# power.net
KiCad netlist of a schematic drawn in Altium Designer
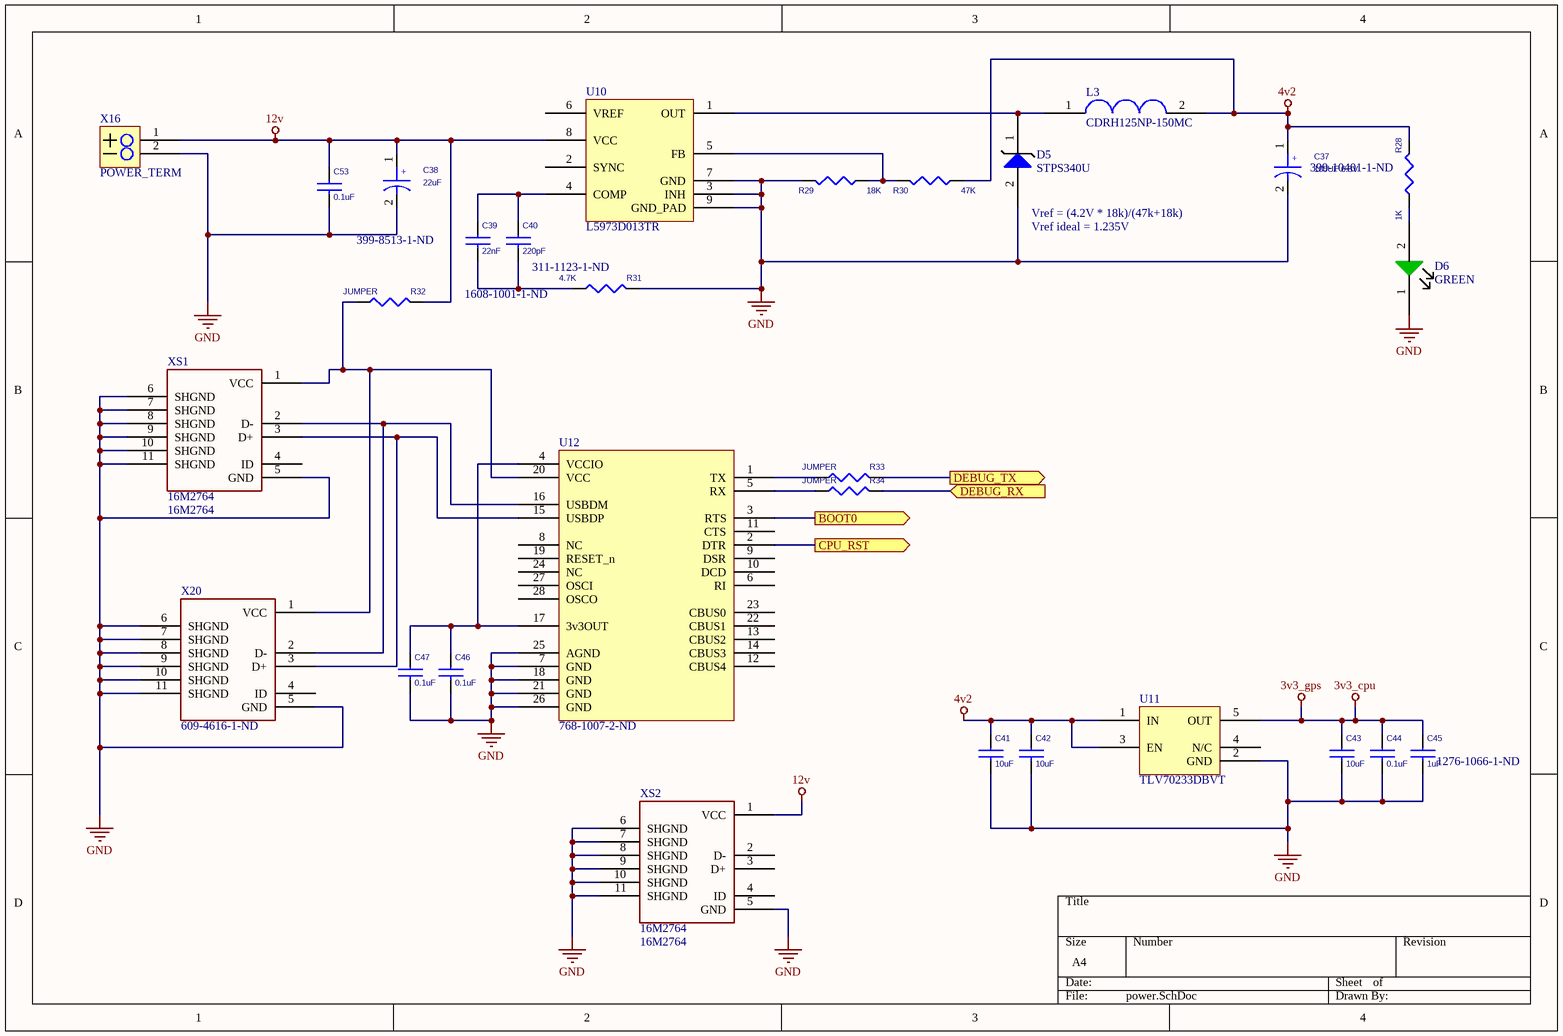
[diagram p0: power.SchDoc]

(export (version "E")
  (design (tool "Eeschema 10.0.6"))
  (components
    (comp (ref "C37")
      (value "100UF 6.3V")
      (footprint "CAPMP6133X31N")
      (description "CAP 100uF; 6.3V; Case: C; ESR:150mOhm")
      (fields (field (name "SUPPLIER PART NUMBER 1") "399-10401-1-ND"))
      (libsource (lib "Capacitors") (part "CAP_SMD_100UF_10%"))
    )
    (comp (ref "C38")
      (value "22uF")
      (footprint "CAPMP7143X31N")
      (description "CAP SMD 35volts 22uF 10% ESR=300mOhms")
      (fields (field (name "SUPPLIER PART NUMBER 1") "399-8513-1-ND"))
      (libsource (lib "Capacitors") (part "CAP_SMD_22UF_10%"))
    )
    (comp (ref "C39")
      (value "22nF")
      (footprint "CAPC2012X09M")
      (description "CAP 22NF 50V 10% X7R 0805")
      (fields (field (name "SUPPLIER PART NUMBER 1") "1608-1001-1-ND"))
      (libsource (lib "Capacitors") (part "CAP_SMD_22nF_10%"))
    )
    (comp (ref "C40")
      (value "220pF")
      (footprint "CAPC2012X09M")
      (description "CAP 220PF 50V 10%  0805")
      (fields (field (name "SUPPLIER PART NUMBER 1") "311-1123-1-ND"))
      (libsource (lib "Capacitors") (part "CAP_SMD_220pF_10%"))
    )
    (comp (ref "C41")
      (value "10uF")
      (footprint "CAPC2012X09M")
      (description "CAP CER 10UF 16V 20% X5R 0805")
      (libsource (lib "Capacitors") (part "CAP_SMD_10UF_20%"))
    )
    (comp (ref "C42")
      (value "10uF")
      (footprint "CAPC2012X09M")
      (description "CAP CER 10UF 16V 20% X5R 0805")
      (libsource (lib "Capacitors") (part "CAP_SMD_10UF_20%"))
    )
    (comp (ref "C43")
      (value "10uF")
      (footprint "CAPC2012X09M")
      (description "CAP CER 10UF 16V 20% X5R 0805")
      (libsource (lib "Capacitors") (part "CAP_SMD_10UF_20%"))
    )
    (comp (ref "C44")
      (value "0.1uF")
      (footprint "CAPC2012X09M")
      (description "CAP CER 0.1UF 25V 10% X7R 0805")
      (libsource (lib "Capacitors") (part "CAP_SMD_0.1UF_10%"))
    )
    (comp (ref "C45")
      (value "1uF")
      (footprint "CAPC2012X09M")
      (description "MLCC; 1uF; 25V; X7R; ±10%; SMD; 0805;")
      (fields (field (name "SUPPLIER PART NUMBER 1") "1276-1066-1-ND"))
      (libsource (lib "Capacitors") (part "CAP_SMD_1uF_10%"))
    )
    (comp (ref "C46")
      (value "0.1uF")
      (footprint "CAPC2012X09M")
      (description "CAP CER 0.1UF 25V 10% X7R 0805")
      (libsource (lib "Capacitors") (part "CAP_SMD_0.1UF_10%"))
    )
    (comp (ref "C47")
      (value "0.1uF")
      (footprint "CAPC2012X09M")
      (description "CAP CER 0.1UF 25V 10% X7R 0805")
      (libsource (lib "Capacitors") (part "CAP_SMD_0.1UF_10%"))
    )
    (comp (ref "C53")
      (value "0.1uF")
      (footprint "CAPC2012X09M")
      (description "CAP CER 0.1UF 25V 10% X7R 0805")
      (libsource (lib "Capacitors") (part "CAP_SMD_0.1UF_10%"))
    )
    (comp (ref "D5")
      (value "STPS340U")
      (footprint "SODFL535X265-2N")
      (description "DIODE, ZENER, 20V, 3W")
      (libsource (lib "Passive") (part "STPS340U"))
    )
    (comp (ref "D6")
      (value "GREEN")
      (footprint "DIOC2012X11N")
      (libsource (lib "Passive") (part "LED_GREEN"))
    )
    (comp (ref "L3")
      (value "CDRH125NP-150MC")
      (footprint "INDP123123X40N_SUMIDA")
      (libsource (lib "Passive") (part "IND_15uH_3.3A"))
    )
    (comp (ref "R28")
      (value "1K")
      (footprint "RESC2013X06M")
      (description "RES - 1K OHM, 5%, 1/8W, 0805 SMD")
      (libsource (lib "Resistors") (part "RES_SMD_1K_5%"))
    )
    (comp (ref "R29")
      (value "18K")
      (footprint "RESC2013X06M")
      (description "RES 18K OHM 1/8W 1% 0805 SMD")
      (libsource (lib "Resistors") (part "RES_SMD_18K_1%"))
    )
    (comp (ref "R30")
      (value "47K")
      (footprint "RESC2013X06M")
      (description "RES 47K OHM 1/8W 1% 0805")
      (libsource (lib "Resistors") (part "RES_SMD_47K_1%"))
    )
    (comp (ref "R31")
      (value "4.7K")
      (footprint "RESC2013X06M")
      (description "RES 4.7K OHM 1/8W 1% 0805 SMD")
      (libsource (lib "Resistors") (part "RES_SMD_4.7K_1%"))
    )
    (comp (ref "R32")
      (value "JUMPER")
      (footprint "RESC2013X06M_CMEASURE")
      (description "RES 0.0 OHM 1/8W JUMP 0805 SMD")
      (libsource (lib "Resistors") (part "RES_SMD_0_CURRENT"))
    )
    (comp (ref "R33")
      (value "JUMPER")
      (footprint "RESC2013X06M_CMEASURE")
      (description "RES 0.0 OHM 1/8W JUMP 0805 SMD")
      (libsource (lib "Resistors") (part "RES_SMD_0_CURRENT"))
    )
    (comp (ref "R34")
      (value "JUMPER")
      (footprint "RESC2013X06M_CMEASURE")
      (description "RES 0.0 OHM 1/8W JUMP 0805 SMD")
      (libsource (lib "Resistors") (part "RES_SMD_0_CURRENT"))
    )
    (comp (ref "U10")
      (value "L5973D013TR")
      (footprint "SOIC127P600X175_HS-9N")
      (description "IC REG BUCK ADJ 2.5A SOIC8")
      (libsource (lib "TruthEar") (part "L5973D013TR"))
    )
    (comp (ref "U11")
      (value "TLV70233DBVT")
      (footprint "SOT95P280X145-5M")
      (libsource (lib "TruthEar") (part "TLV70233DBVT"))
    )
    (comp (ref "U12")
      (value "FT232RL")
      (footprint "SOP65P780X200-28M")
      (fields (field (name "SUPPLIER PART NUMBER 1") "768-1007-2-ND"))
      (libsource (lib "TruthEar") (part "FT232RL"))
    )
    (comp (ref "X16")
      (value "POWER_TERM")
      (footprint "PH5")
      (libsource (lib "Connectors") (part "POWER_TERM"))
    )
    (comp (ref "X20")
      (value "10118193-0001LF")
      (footprint "USB_MICRO_10118193")
      (fields (field (name "SUPPLIER PART NUMBER 1") "609-4616-1-ND"))
      (libsource (lib "Connectors") (part "USB_MICRO"))
    )
    (comp (ref "XS1")
      (value "16M2764")
      (footprint "USB_MINI_16M2764")
      (fields (field (name "SUPPLIER PART NUMBER 1") "16M2764"))
      (libsource (lib "Connectors") (part "USB_MINI_16M2764"))
    )
    (comp (ref "XS2")
      (value "16M2764")
      (footprint "USB_MINI_16M2764")
      (fields (field (name "SUPPLIER PART NUMBER 1") "16M2764"))
      (libsource (lib "Connectors") (part "USB_MINI_16M2764"))
    )
  )
  (nets
    (net (code "1") (name "/BOOT0") (class "Default")
      (node (ref "U12") (pin "3") (pinfunction "RTS_3") (pintype "power_in"))
    )
    (net (code "2") (name "/CPU_RST") (class "Default")
      (node (ref "U12") (pin "2") (pinfunction "DTR_2") (pintype "power_in"))
    )
    (net (code "3") (name "/DEBUG_RX") (class "Default")
      (node (ref "R34") (pin "2") (pinfunction "2_2") (pintype "passive"))
    )
    (net (code "4") (name "/DEBUG_TX") (class "Default")
      (node (ref "R33") (pin "2") (pinfunction "2_2") (pintype "passive"))
    )
    (net (code "5") (name "3v3_cpu") (class "Default")
      (node (ref "C43") (pin "1") (pinfunction "1_1") (pintype "passive"))
      (node (ref "C44") (pin "1") (pinfunction "1_1") (pintype "passive"))
      (node (ref "C45") (pin "1") (pinfunction "1_1") (pintype "passive"))
      (node (ref "U11") (pin "5") (pinfunction "OUT_5") (pintype "passive"))
    )
    (net (code "6") (name "4v2") (class "Default")
      (node (ref "C37") (pin "1") (pinfunction "1_1") (pintype "passive"))
      (node (ref "C41") (pin "1") (pinfunction "1_1") (pintype "passive"))
      (node (ref "C42") (pin "1") (pinfunction "1_1") (pintype "passive"))
      (node (ref "L3") (pin "2") (pinfunction "2_2") (pintype "passive"))
      (node (ref "R28") (pin "2") (pinfunction "2_2") (pintype "passive"))
      (node (ref "R30") (pin "1") (pinfunction "1_1") (pintype "passive"))
      (node (ref "U11") (pin "1") (pinfunction "IN_1") (pintype "passive"))
      (node (ref "U11") (pin "3") (pinfunction "EN_3") (pintype "passive"))
    )
    (net (code "7") (name "12v") (class "Default")
      (node (ref "C38") (pin "1") (pinfunction "1_1") (pintype "passive"))
      (node (ref "C53") (pin "1") (pinfunction "1_1") (pintype "passive"))
      (node (ref "R32") (pin "2") (pinfunction "2_2") (pintype "passive"))
      (node (ref "U10") (pin "8") (pinfunction "VCC_8") (pintype "passive"))
      (node (ref "X16") (pin "1") (pinfunction "1_1") (pintype "passive"))
      (node (ref "XS2") (pin "1") (pinfunction "VCC_1") (pintype "passive"))
    )
    (net (code "8") (name "GND") (class "Default")
      (node (ref "C37") (pin "2") (pinfunction "2_2") (pintype "passive"))
      (node (ref "C38") (pin "2") (pinfunction "2_2") (pintype "passive"))
      (node (ref "C41") (pin "2") (pinfunction "2_2") (pintype "passive"))
      (node (ref "C42") (pin "2") (pinfunction "2_2") (pintype "passive"))
      (node (ref "C43") (pin "2") (pinfunction "2_2") (pintype "passive"))
      (node (ref "C44") (pin "2") (pinfunction "2_2") (pintype "passive"))
      (node (ref "C45") (pin "2") (pinfunction "2_2") (pintype "passive"))
      (node (ref "C46") (pin "2") (pinfunction "2_2") (pintype "passive"))
      (node (ref "C47") (pin "2") (pinfunction "2_2") (pintype "passive"))
      (node (ref "C53") (pin "2") (pinfunction "2_2") (pintype "passive"))
      (node (ref "D5") (pin "2") (pinfunction "A_2") (pintype "passive"))
      (node (ref "D6") (pin "1") (pinfunction "C_1") (pintype "passive"))
      (node (ref "R29") (pin "2") (pinfunction "2_2") (pintype "passive"))
      (node (ref "R31") (pin "2") (pinfunction "2_2") (pintype "passive"))
      (node (ref "U10") (pin "3") (pinfunction "INH_3") (pintype "passive"))
      (node (ref "U10") (pin "7") (pinfunction "GND_7") (pintype "passive"))
      (node (ref "U10") (pin "9") (pinfunction "GND_PAD_9") (pintype "passive"))
      (node (ref "U11") (pin "2") (pinfunction "GND_2") (pintype "passive"))
      (node (ref "U12") (pin "18") (pinfunction "GND_18") (pintype "power_in"))
      (node (ref "U12") (pin "21") (pinfunction "GND_21") (pintype "power_in"))
      (node (ref "U12") (pin "25") (pinfunction "AGND_25") (pintype "power_in"))
      (node (ref "U12") (pin "26") (pinfunction "GND_26") (pintype "power_in"))
      (node (ref "U12") (pin "7") (pinfunction "GND_7") (pintype "power_in"))
      (node (ref "X16") (pin "2") (pinfunction "2_2") (pintype "passive"))
      (node (ref "X20") (pin "10") (pinfunction "SHGND_10") (pintype "passive"))
      (node (ref "X20") (pin "11") (pinfunction "SHGND_11") (pintype "passive"))
      (node (ref "X20") (pin "5") (pinfunction "GND_5") (pintype "passive"))
      (node (ref "X20") (pin "6") (pinfunction "SHGND_6") (pintype "passive"))
      (node (ref "X20") (pin "7") (pinfunction "SHGND_7") (pintype "passive"))
      (node (ref "X20") (pin "8") (pinfunction "SHGND_8") (pintype "passive"))
      (node (ref "X20") (pin "9") (pinfunction "SHGND_9") (pintype "passive"))
      (node (ref "XS1") (pin "10") (pinfunction "SHGND_10") (pintype "passive"))
      (node (ref "XS1") (pin "11") (pinfunction "SHGND_11") (pintype "passive"))
      (node (ref "XS1") (pin "5") (pinfunction "GND_5") (pintype "passive"))
      (node (ref "XS1") (pin "6") (pinfunction "SHGND_6") (pintype "passive"))
      (node (ref "XS1") (pin "7") (pinfunction "SHGND_7") (pintype "passive"))
      (node (ref "XS1") (pin "8") (pinfunction "SHGND_8") (pintype "passive"))
      (node (ref "XS1") (pin "9") (pinfunction "SHGND_9") (pintype "passive"))
      (node (ref "XS2") (pin "10") (pinfunction "SHGND_10") (pintype "passive"))
      (node (ref "XS2") (pin "11") (pinfunction "SHGND_11") (pintype "passive"))
      (node (ref "XS2") (pin "5") (pinfunction "GND_5") (pintype "passive"))
      (node (ref "XS2") (pin "6") (pinfunction "SHGND_6") (pintype "passive"))
      (node (ref "XS2") (pin "7") (pinfunction "SHGND_7") (pintype "passive"))
      (node (ref "XS2") (pin "8") (pinfunction "SHGND_8") (pintype "passive"))
      (node (ref "XS2") (pin "9") (pinfunction "SHGND_9") (pintype "passive"))
    )
    (net (code "9") (name "Net-(C39-Pad2)") (class "Default")
      (node (ref "C39") (pin "2") (pinfunction "2_2") (pintype "passive"))
      (node (ref "C40") (pin "2") (pinfunction "2_2") (pintype "passive"))
      (node (ref "R31") (pin "1") (pinfunction "1_1") (pintype "passive"))
    )
    (net (code "10") (name "Net-(D5-C)") (class "Default")
      (node (ref "D5") (pin "1") (pinfunction "C_1") (pintype "passive"))
      (node (ref "L3") (pin "1") (pinfunction "1_1") (pintype "passive"))
      (node (ref "U10") (pin "1") (pinfunction "OUT_1") (pintype "passive"))
    )
    (net (code "11") (name "Net-(D6-A)") (class "Default")
      (node (ref "D6") (pin "2") (pinfunction "A_2") (pintype "passive"))
      (node (ref "R28") (pin "1") (pinfunction "1_1") (pintype "passive"))
    )
    (net (code "12") (name "Net-(U10-COMP)") (class "Default")
      (node (ref "C39") (pin "1") (pinfunction "1_1") (pintype "passive"))
      (node (ref "C40") (pin "1") (pinfunction "1_1") (pintype "passive"))
      (node (ref "U10") (pin "4") (pinfunction "COMP_4") (pintype "passive"))
    )
    (net (code "13") (name "Net-(U10-FB)") (class "Default")
      (node (ref "R29") (pin "1") (pinfunction "1_1") (pintype "passive"))
      (node (ref "R30") (pin "2") (pinfunction "2_2") (pintype "passive"))
      (node (ref "U10") (pin "5") (pinfunction "FB_5") (pintype "passive"))
    )
    (net (code "14") (name "Net-(U12-3v3OUT)") (class "Default")
      (node (ref "C46") (pin "1") (pinfunction "1_1") (pintype "passive"))
      (node (ref "C47") (pin "1") (pinfunction "1_1") (pintype "passive"))
      (node (ref "U12") (pin "17") (pinfunction "3v3OUT_17") (pintype "power_in"))
      (node (ref "U12") (pin "4") (pinfunction "VCCIO_4") (pintype "power_in"))
    )
    (net (code "15") (name "Net-(U12-RX)") (class "Default")
      (node (ref "R34") (pin "1") (pinfunction "1_1") (pintype "passive"))
      (node (ref "U12") (pin "5") (pinfunction "RX_5") (pintype "power_in"))
    )
    (net (code "16") (name "Net-(U12-TX)") (class "Default")
      (node (ref "R33") (pin "1") (pinfunction "1_1") (pintype "passive"))
      (node (ref "U12") (pin "1") (pinfunction "TX_1") (pintype "power_in"))
    )
    (net (code "17") (name "Net-(U12-USBDM)") (class "Default")
      (node (ref "U12") (pin "16") (pinfunction "USBDM_16") (pintype "power_in"))
      (node (ref "X20") (pin "2") (pinfunction "D-_2") (pintype "passive"))
      (node (ref "XS1") (pin "2") (pinfunction "D-_2") (pintype "passive"))
    )
    (net (code "18") (name "Net-(U12-USBDP)") (class "Default")
      (node (ref "U12") (pin "15") (pinfunction "USBDP_15") (pintype "power_in"))
      (node (ref "X20") (pin "3") (pinfunction "D+_3") (pintype "passive"))
      (node (ref "XS1") (pin "3") (pinfunction "D+_3") (pintype "passive"))
    )
    (net (code "19") (name "Net-(U12-VCC)") (class "Default")
      (node (ref "R32") (pin "1") (pinfunction "1_1") (pintype "passive"))
      (node (ref "U12") (pin "20") (pinfunction "VCC_20") (pintype "power_in"))
      (node (ref "X20") (pin "1") (pinfunction "VCC_1") (pintype "passive"))
      (node (ref "XS1") (pin "1") (pinfunction "VCC_1") (pintype "passive"))
    )
    (net (code "20") (name "unconnected-(U10-SYNC-Pad2)") (class "Default")
      (node (ref "U10") (pin "2") (pinfunction "SYNC_2") (pintype "passive"))
    )
    (net (code "21") (name "unconnected-(U10-VREF-Pad6)") (class "Default")
      (node (ref "U10") (pin "6") (pinfunction "VREF_6") (pintype "passive"))
    )
    (net (code "22") (name "unconnected-(U11-N{slash}C-Pad4)") (class "Default")
      (node (ref "U11") (pin "4") (pinfunction "N/C_4") (pintype "passive"))
    )
    (net (code "23") (name "unconnected-(U12-CBUS0-Pad23)") (class "Default")
      (node (ref "U12") (pin "23") (pinfunction "CBUS0_23") (pintype "power_in"))
    )
    (net (code "24") (name "unconnected-(U12-CBUS1-Pad22)") (class "Default")
      (node (ref "U12") (pin "22") (pinfunction "CBUS1_22") (pintype "power_in"))
    )
    (net (code "25") (name "unconnected-(U12-CBUS2-Pad13)") (class "Default")
      (node (ref "U12") (pin "13") (pinfunction "CBUS2_13") (pintype "power_in"))
    )
    (net (code "26") (name "unconnected-(U12-CBUS3-Pad14)") (class "Default")
      (node (ref "U12") (pin "14") (pinfunction "CBUS3_14") (pintype "power_in"))
    )
    (net (code "27") (name "unconnected-(U12-CBUS4-Pad12)") (class "Default")
      (node (ref "U12") (pin "12") (pinfunction "CBUS4_12") (pintype "power_in"))
    )
    (net (code "28") (name "unconnected-(U12-CTS-Pad11)") (class "Default")
      (node (ref "U12") (pin "11") (pinfunction "CTS_11") (pintype "power_in"))
    )
    (net (code "29") (name "unconnected-(U12-DCD-Pad10)") (class "Default")
      (node (ref "U12") (pin "10") (pinfunction "DCD_10") (pintype "power_in"))
    )
    (net (code "30") (name "unconnected-(U12-DSR-Pad9)") (class "Default")
      (node (ref "U12") (pin "9") (pinfunction "DSR_9") (pintype "power_in"))
    )
    (net (code "31") (name "unconnected-(U12-NC-Pad8)") (class "Default")
      (node (ref "U12") (pin "8") (pinfunction "NC_8") (pintype "power_in"))
    )
    (net (code "32") (name "unconnected-(U12-NC-Pad24)") (class "Default")
      (node (ref "U12") (pin "24") (pinfunction "NC_24") (pintype "power_in"))
    )
    (net (code "33") (name "unconnected-(U12-OSCI-Pad27)") (class "Default")
      (node (ref "U12") (pin "27") (pinfunction "OSCI_27") (pintype "power_in"))
    )
    (net (code "34") (name "unconnected-(U12-OSCO-Pad28)") (class "Default")
      (node (ref "U12") (pin "28") (pinfunction "OSCO_28") (pintype "power_in"))
    )
    (net (code "35") (name "unconnected-(U12-RESET_n-Pad19)") (class "Default")
      (node (ref "U12") (pin "19") (pinfunction "RESET_n_19") (pintype "power_in"))
    )
    (net (code "36") (name "unconnected-(U12-RI-Pad6)") (class "Default")
      (node (ref "U12") (pin "6") (pinfunction "RI_6") (pintype "power_in"))
    )
    (net (code "37") (name "unconnected-(X20-ID-Pad4)") (class "Default")
      (node (ref "X20") (pin "4") (pinfunction "ID_4") (pintype "passive"))
    )
    (net (code "38") (name "unconnected-(XS1-ID-Pad4)") (class "Default")
      (node (ref "XS1") (pin "4") (pinfunction "ID_4") (pintype "passive"))
    )
    (net (code "39") (name "unconnected-(XS2-D+-Pad3)") (class "Default")
      (node (ref "XS2") (pin "3") (pinfunction "D+_3") (pintype "passive"))
    )
    (net (code "40") (name "unconnected-(XS2-D--Pad2)") (class "Default")
      (node (ref "XS2") (pin "2") (pinfunction "D-_2") (pintype "passive"))
    )
    (net (code "41") (name "unconnected-(XS2-ID-Pad4)") (class "Default")
      (node (ref "XS2") (pin "4") (pinfunction "ID_4") (pintype "passive"))
    )
  )
)
